# mainboard.net
KiCad netlist of a schematic drawn in EAGLE
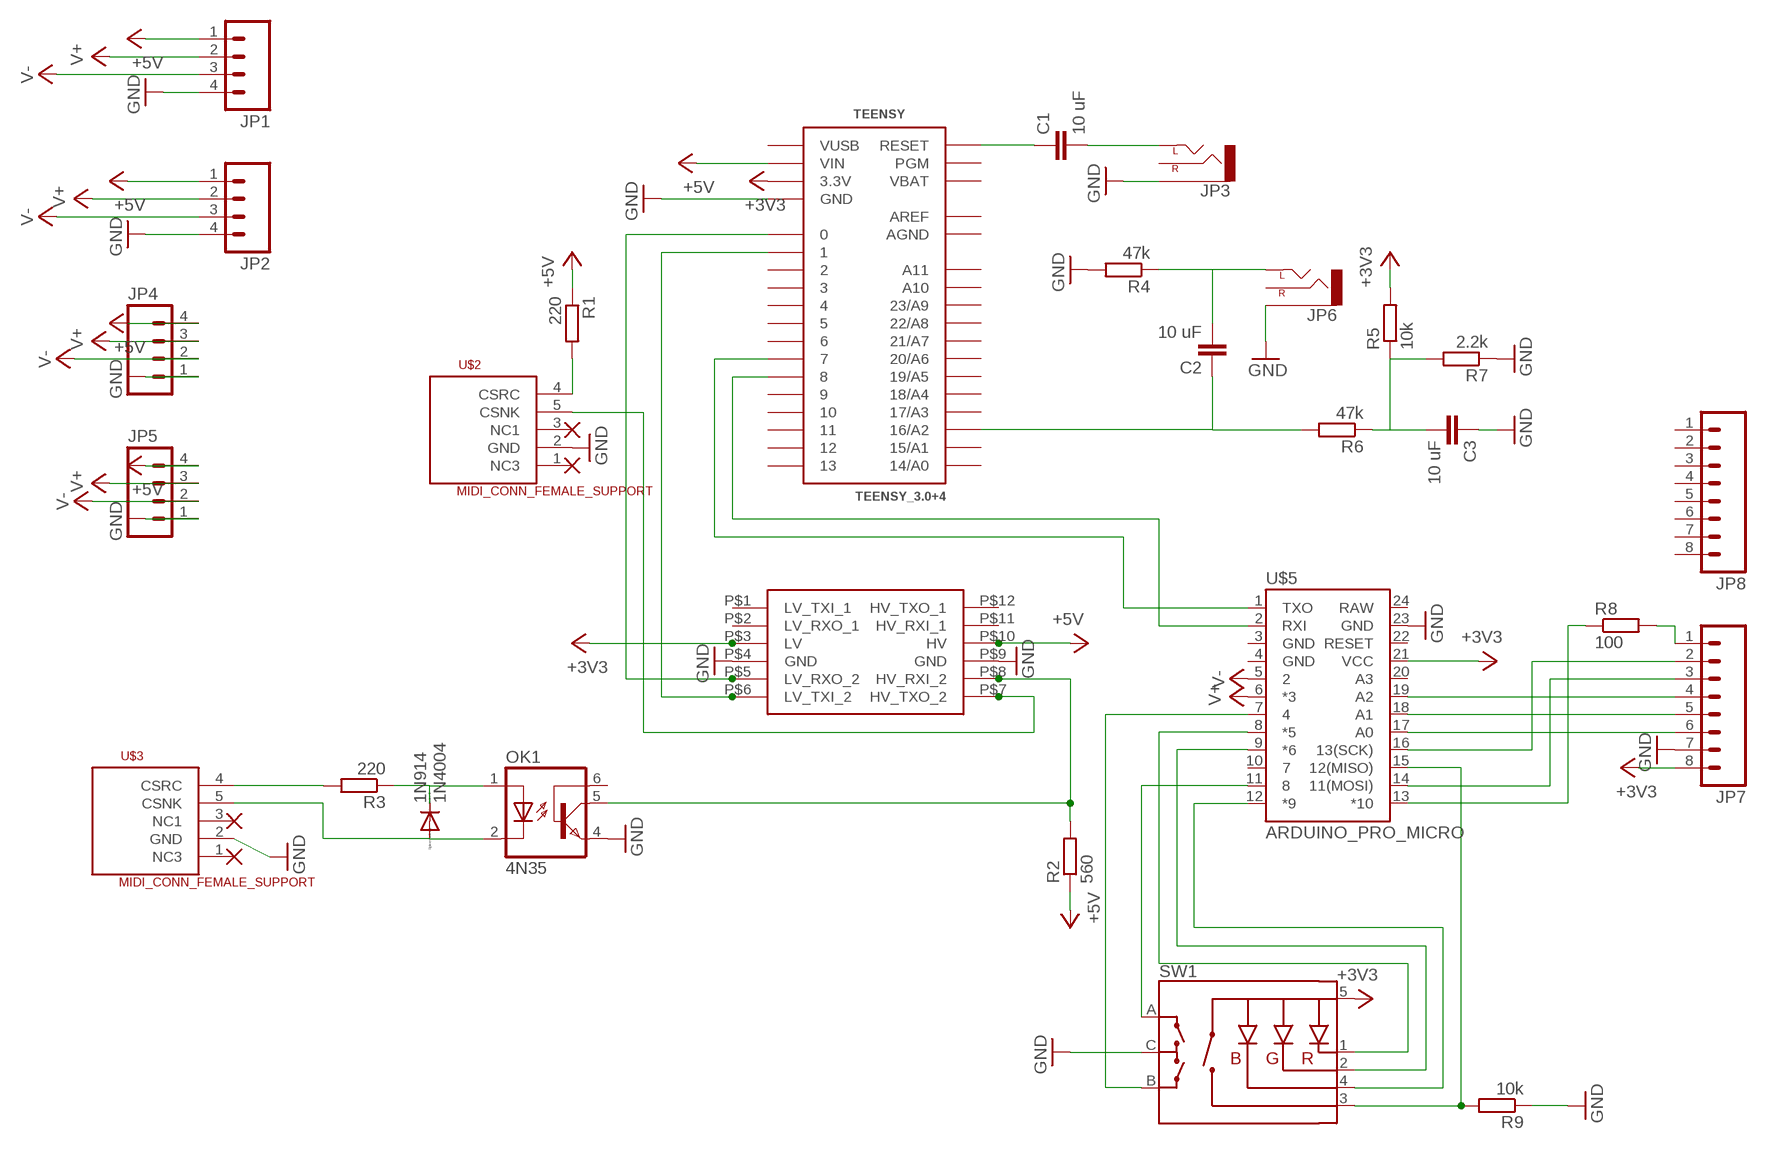
[diagram p0: schematic, sheet 1]

(export (version "E")
  (design (tool "Eeschema 10.0.6"))
  (components
    (comp (ref "1N914")
      (value "1N4004")
      (footprint "eagle-import:DO41-10")
      (libsource (lib "eagle-import") (part "1N4004"))
    )
    (comp (ref "C1")
      (value "10 uF")
      (footprint "eagle-import:CAP-PTH-SMALL")
      (libsource (lib "eagle-import") (part "CAPPTH"))
    )
    (comp (ref "C2")
      (value "10 uF")
      (footprint "eagle-import:CAP-PTH-SMALL")
      (libsource (lib "eagle-import") (part "CAPPTH"))
    )
    (comp (ref "C3")
      (value "10 uF")
      (footprint "eagle-import:CAP-PTH-SMALL")
      (libsource (lib "eagle-import") (part "CAPPTH"))
    )
    (comp (ref "JP1")
      (value "M04PTH")
      (footprint "eagle-import:1X04")
      (libsource (lib "eagle-import") (part "M04PTH"))
    )
    (comp (ref "JP2")
      (value "M04PTH")
      (footprint "eagle-import:1X04")
      (libsource (lib "eagle-import") (part "M04PTH"))
    )
    (comp (ref "JP3")
      (value "AUDIO-JACKPTH")
      (footprint "eagle-import:AUDIO-JACK")
      (libsource (lib "eagle-import") (part "AUDIO-JACKPTH"))
    )
    (comp (ref "JP4")
      (value "M04PTH")
      (footprint "eagle-import:1X04")
      (libsource (lib "eagle-import") (part "M04PTH"))
    )
    (comp (ref "JP5")
      (value "M04PTH")
      (footprint "eagle-import:1X04")
      (libsource (lib "eagle-import") (part "M04PTH"))
    )
    (comp (ref "JP6")
      (value "AUDIO-JACKPTH")
      (footprint "eagle-import:AUDIO-JACK")
      (libsource (lib "eagle-import") (part "AUDIO-JACKPTH"))
    )
    (comp (ref "JP7")
      (value "M08")
      (footprint "eagle-import:1X08_ROUND")
      (libsource (lib "eagle-import") (part "M08"))
    )
    (comp (ref "JP8")
      (value "M08")
      (footprint "eagle-import:1X08_ROUND")
      (libsource (lib "eagle-import") (part "M08"))
    )
    (comp (ref "OK1")
      (value "4N35")
      (footprint "eagle-import:DIL06")
      (fields (field (name "MF") "FAIRCHILD SEMICONDUCTOR"))
      (libsource (lib "eagle-import") (part "4N35"))
    )
    (comp (ref "R1")
      (value "220")
      (footprint "eagle-import:0204_5")
      (libsource (lib "eagle-import") (part "R-EU_0204/5"))
    )
    (comp (ref "R2")
      (value "560")
      (footprint "eagle-import:0204_5")
      (libsource (lib "eagle-import") (part "R-EU_0204/5"))
    )
    (comp (ref "R3")
      (value "220")
      (footprint "eagle-import:0204_5")
      (libsource (lib "eagle-import") (part "R-EU_0204/5"))
    )
    (comp (ref "R4")
      (value "47k")
      (footprint "eagle-import:0204_5")
      (libsource (lib "eagle-import") (part "R-EU_0204/5"))
    )
    (comp (ref "R5")
      (value "10k")
      (footprint "eagle-import:0204_5")
      (libsource (lib "eagle-import") (part "R-EU_0204/5"))
    )
    (comp (ref "R6")
      (value "47k")
      (footprint "eagle-import:0204_5")
      (libsource (lib "eagle-import") (part "R-EU_0204/5"))
    )
    (comp (ref "R7")
      (value "2.2k")
      (footprint "eagle-import:0204_5")
      (libsource (lib "eagle-import") (part "R-EU_0204/5"))
    )
    (comp (ref "R8")
      (value "100")
      (footprint "eagle-import:0204_5")
      (libsource (lib "eagle-import") (part "R-EU_0204/5"))
    )
    (comp (ref "R9")
      (value "10k")
      (footprint "eagle-import:0204_5")
      (libsource (lib "eagle-import") (part "R-EU_0204/5"))
    )
    (comp (ref "SW1")
      (value "ENCODER_RGB_CA")
      (footprint "eagle-import:ENCODER_LED_3")
      (libsource (lib "eagle-import") (part "ENCODER_RGB_CA"))
    )
    (comp (ref "TEENSY")
      (value "TEENSY_3.0+4")
      (footprint "eagle-import:TEENSY_3.0+4")
      (libsource (lib "eagle-import") (part "TEENSY_3.0+4"))
    )
    (comp (ref "U$2")
      (value "MIDI_CONN_FEMALE_SUPPORT")
      (footprint "eagle-import:DIN_5_FEMALE_SUPPORT")
      (libsource (lib "eagle-import") (part "MIDI_CONN_FEMALE_SUPPORT"))
    )
    (comp (ref "U$3")
      (value "MIDI_CONN_FEMALE_SUPPORT")
      (footprint "eagle-import:DIN_5_FEMALE_SUPPORT")
      (libsource (lib "eagle-import") (part "MIDI_CONN_FEMALE_SUPPORT"))
    )
    (comp (ref "U$4")
      (value "LOGIC_LEVEL_CONVERTER")
      (footprint "eagle-import:LOGIC_LEVEL_CONVERTER")
      (libsource (lib "eagle-import") (part "LOGIC_LEVEL_CONVERTER"))
    )
    (comp (ref "U$5")
      (value "ARDUINO_PRO_MICRO")
      (footprint "eagle-import:ARDUINO_PRO_MICRO")
      (libsource (lib "eagle-import") (part "ARDUINO_PRO_MICRO"))
    )
  )
  (nets
    (net (code "1") (name "+3V3") (class "Default")
      (node (ref "JP7") (pin "8") (pinfunction "8_8") (pintype "passive"))
      (node (ref "R5") (pin "2") (pinfunction "2_2") (pintype "passive"))
      (node (ref "SW1") (pin "5") (pinfunction "+_5") (pintype "passive"))
      (node (ref "TEENSY") (pin "3.3V") (pinfunction "3.3V_3.3V") (pintype "power_in"))
      (node (ref "TEENSY") (pin "3.3V1") (pinfunction "3.3V_3.3V1") (pintype "power_in"))
      (node (ref "U$4") (pin "P$3") (pinfunction "LV_P$3") (pintype "bidirectional"))
      (node (ref "U$5") (pin "21") (pinfunction "VCC_21") (pintype "bidirectional"))
    )
    (net (code "2") (name "+5V") (class "Default")
      (node (ref "JP1") (pin "1") (pinfunction "1_1") (pintype "passive"))
      (node (ref "JP2") (pin "1") (pinfunction "1_1") (pintype "passive"))
      (node (ref "JP4") (pin "4") (pinfunction "4_4") (pintype "passive"))
      (node (ref "JP5") (pin "4") (pinfunction "4_4") (pintype "passive"))
      (node (ref "R1") (pin "1") (pinfunction "1_1") (pintype "passive"))
      (node (ref "R2") (pin "1") (pinfunction "1_1") (pintype "passive"))
      (node (ref "TEENSY") (pin "VIN") (pinfunction "VIN_VIN") (pintype "power_in"))
      (node (ref "U$4") (pin "P$10") (pinfunction "HV_P$10") (pintype "bidirectional"))
    )
    (net (code "3") (name "/AGND") (class "Default")
      (node (ref "TEENSY") (pin "AGND") (pinfunction "AGND_AGND") (pintype "power_in"))
    )
    (net (code "4") (name "/AREF") (class "Default")
      (node (ref "TEENSY") (pin "AREF") (pinfunction "AREF_AREF") (pintype "power_in"))
    )
    (net (code "5") (name "/VBAT") (class "Default")
      (node (ref "TEENSY") (pin "VBAT") (pinfunction "VBAT_VBAT") (pintype "power_in"))
    )
    (net (code "6") (name "/VUSB") (class "Default")
      (node (ref "TEENSY") (pin "VUSB") (pinfunction "VUSB_VUSB") (pintype "power_in"))
    )
    (net (code "7") (name "GND") (class "Default")
      (node (ref "C3") (pin "1") (pinfunction "1_1") (pintype "passive"))
      (node (ref "JP1") (pin "4") (pinfunction "4_4") (pintype "passive"))
      (node (ref "JP2") (pin "4") (pinfunction "4_4") (pintype "passive"))
      (node (ref "JP3") (pin "SLEEVE") (pinfunction "SLEEVE_SLEEVE") (pintype "bidirectional"))
      (node (ref "JP4") (pin "1") (pinfunction "1_1") (pintype "passive"))
      (node (ref "JP5") (pin "1") (pinfunction "1_1") (pintype "passive"))
      (node (ref "JP6") (pin "SLEEVE") (pinfunction "SLEEVE_SLEEVE") (pintype "bidirectional"))
      (node (ref "JP7") (pin "7") (pinfunction "7_7") (pintype "passive"))
      (node (ref "OK1") (pin "4") (pinfunction "EMI_4") (pintype "passive"))
      (node (ref "R4") (pin "2") (pinfunction "2_2") (pintype "passive"))
      (node (ref "R7") (pin "1") (pinfunction "1_1") (pintype "passive"))
      (node (ref "R9") (pin "1") (pinfunction "1_1") (pintype "passive"))
      (node (ref "SW1") (pin "C") (pinfunction "C_C") (pintype "bidirectional"))
      (node (ref "TEENSY") (pin "GND") (pinfunction "GND_GND") (pintype "power_in"))
      (node (ref "TEENSY") (pin "GND1") (pinfunction "GND_GND1") (pintype "power_in"))
      (node (ref "U$2") (pin "2") (pinfunction "GND_2") (pintype "bidirectional"))
      (node (ref "U$3") (pin "2") (pinfunction "GND_2") (pintype "bidirectional"))
      (node (ref "U$4") (pin "P$4") (pinfunction "GND_P$4") (pintype "bidirectional"))
      (node (ref "U$4") (pin "P$9") (pinfunction "GND_P$9") (pintype "bidirectional"))
      (node (ref "U$5") (pin "23") (pinfunction "GND_23") (pintype "bidirectional"))
    )
    (net (code "8") (name "Net-(C1-Pad1)") (class "Default")
      (node (ref "C1") (pin "1") (pinfunction "1_1") (pintype "passive"))
      (node (ref "TEENSY") (pin "RESET") (pinfunction "RESET_RESET") (pintype "bidirectional"))
    )
    (net (code "9") (name "Net-(C2-Pad1)") (class "Default")
      (node (ref "C2") (pin "1") (pinfunction "1_1") (pintype "passive"))
      (node (ref "R6") (pin "2") (pinfunction "2_2") (pintype "passive"))
      (node (ref "TEENSY") (pin "16/A2") (pinfunction "16/A2_16/A2") (pintype "bidirectional"))
    )
    (net (code "10") (name "Net-(C3-Pad2)") (class "Default")
      (node (ref "C3") (pin "2") (pinfunction "2_2") (pintype "passive"))
      (node (ref "R5") (pin "1") (pinfunction "1_1") (pintype "passive"))
      (node (ref "R6") (pin "1") (pinfunction "1_1") (pintype "passive"))
      (node (ref "R7") (pin "2") (pinfunction "2_2") (pintype "passive"))
    )
    (net (code "11") (name "Net-(JP3-LEFT)") (class "Default")
      (node (ref "C1") (pin "2") (pinfunction "2_2") (pintype "passive"))
      (node (ref "JP3") (pin "TIP") (pinfunction "LEFT_TIP") (pintype "bidirectional"))
    )
    (net (code "12") (name "Net-(JP6-LEFT)") (class "Default")
      (node (ref "C2") (pin "2") (pinfunction "2_2") (pintype "passive"))
      (node (ref "JP6") (pin "TIP") (pinfunction "LEFT_TIP") (pintype "bidirectional"))
      (node (ref "R4") (pin "1") (pinfunction "1_1") (pintype "passive"))
    )
    (net (code "13") (name "Net-(JP7-Pad1)") (class "Default")
      (node (ref "JP7") (pin "1") (pinfunction "1_1") (pintype "passive"))
      (node (ref "R8") (pin "2") (pinfunction "2_2") (pintype "passive"))
    )
    (net (code "14") (name "Net-(OK1-A)") (class "Default")
      (node (ref "1N914") (pin "C") (pinfunction "C_C") (pintype "passive"))
      (node (ref "OK1") (pin "1") (pinfunction "A_1") (pintype "passive"))
      (node (ref "R3") (pin "1") (pinfunction "1_1") (pintype "passive"))
    )
    (net (code "15") (name "Net-(OK1-C)") (class "Default")
      (node (ref "1N914") (pin "A") (pinfunction "A_A") (pintype "passive"))
      (node (ref "OK1") (pin "2") (pinfunction "C_2") (pintype "passive"))
      (node (ref "U$3") (pin "5") (pinfunction "CSNK_5") (pintype "bidirectional"))
    )
    (net (code "16") (name "Net-(OK1-COL)") (class "Default")
      (node (ref "OK1") (pin "5") (pinfunction "COL_5") (pintype "passive"))
      (node (ref "R2") (pin "2") (pinfunction "2_2") (pintype "passive"))
      (node (ref "U$4") (pin "P$8") (pinfunction "HV_RXI_2_P$8") (pintype "bidirectional"))
    )
    (net (code "17") (name "Net-(SW1--B)") (class "Default")
      (node (ref "SW1") (pin "4") (pinfunction "-B_4") (pintype "passive"))
      (node (ref "U$5") (pin "12") (pinfunction "*9_12") (pintype "bidirectional"))
    )
    (net (code "18") (name "Net-(SW1--G)") (class "Default")
      (node (ref "SW1") (pin "2") (pinfunction "-G_2") (pintype "passive"))
      (node (ref "U$5") (pin "9") (pinfunction "*6_9") (pintype "bidirectional"))
    )
    (net (code "19") (name "Net-(SW1--R)") (class "Default")
      (node (ref "SW1") (pin "1") (pinfunction "-R_1") (pintype "passive"))
      (node (ref "U$5") (pin "8") (pinfunction "*5_8") (pintype "bidirectional"))
    )
    (net (code "20") (name "Net-(SW1-SW)") (class "Default")
      (node (ref "R9") (pin "2") (pinfunction "2_2") (pintype "passive"))
      (node (ref "SW1") (pin "3") (pinfunction "SW_3") (pintype "passive"))
      (node (ref "U$5") (pin "15") (pinfunction "12(MISO)_15") (pintype "bidirectional"))
    )
    (net (code "21") (name "Net-(U$2-CSNK)") (class "Default")
      (node (ref "U$2") (pin "5") (pinfunction "CSNK_5") (pintype "bidirectional"))
      (node (ref "U$4") (pin "P$7") (pinfunction "HV_TXO_2_P$7") (pintype "bidirectional"))
    )
    (net (code "22") (name "Net-(U$2-CSRC)") (class "Default")
      (node (ref "R1") (pin "2") (pinfunction "2_2") (pintype "passive"))
      (node (ref "U$2") (pin "4") (pinfunction "CSRC_4") (pintype "bidirectional"))
    )
    (net (code "23") (name "Net-(U$3-CSRC)") (class "Default")
      (node (ref "R3") (pin "2") (pinfunction "2_2") (pintype "passive"))
      (node (ref "U$3") (pin "4") (pinfunction "CSRC_4") (pintype "bidirectional"))
    )
    (net (code "24") (name "Net-(U$4-LV_RXO_2)") (class "Default")
      (node (ref "TEENSY") (pin "0") (pinfunction "0_0") (pintype "bidirectional"))
      (node (ref "U$4") (pin "P$5") (pinfunction "LV_RXO_2_P$5") (pintype "bidirectional"))
    )
    (net (code "25") (name "Net-(U$4-LV_TXI_2)") (class "Default")
      (node (ref "TEENSY") (pin "1") (pinfunction "1_1") (pintype "bidirectional"))
      (node (ref "U$4") (pin "P$6") (pinfunction "LV_TXI_2_P$6") (pintype "bidirectional"))
    )
    (net (code "26") (name "Net-(U$5-*10)") (class "Default")
      (node (ref "R8") (pin "1") (pinfunction "1_1") (pintype "passive"))
      (node (ref "U$5") (pin "13") (pinfunction "*10_13") (pintype "bidirectional"))
    )
    (net (code "27") (name "Net-(U$5-4)") (class "Default")
      (node (ref "SW1") (pin "B") (pinfunction "B_B") (pintype "bidirectional"))
      (node (ref "U$5") (pin "7") (pinfunction "4_7") (pintype "bidirectional"))
    )
    (net (code "28") (name "Net-(U$5-8)") (class "Default")
      (node (ref "SW1") (pin "A") (pinfunction "A_A") (pintype "bidirectional"))
      (node (ref "U$5") (pin "11") (pinfunction "8_11") (pintype "bidirectional"))
    )
    (net (code "29") (name "Net-(U$5-11(MOSI))") (class "Default")
      (node (ref "JP7") (pin "3") (pinfunction "3_3") (pintype "passive"))
      (node (ref "U$5") (pin "14") (pinfunction "11(MOSI)_14") (pintype "bidirectional"))
    )
    (net (code "30") (name "Net-(U$5-13(SCK))") (class "Default")
      (node (ref "JP7") (pin "2") (pinfunction "2_2") (pintype "passive"))
      (node (ref "U$5") (pin "16") (pinfunction "13(SCK)_16") (pintype "bidirectional"))
    )
    (net (code "31") (name "Net-(U$5-A0)") (class "Default")
      (node (ref "JP7") (pin "6") (pinfunction "6_6") (pintype "passive"))
      (node (ref "U$5") (pin "17") (pinfunction "A0_17") (pintype "bidirectional"))
    )
    (net (code "32") (name "Net-(U$5-A1)") (class "Default")
      (node (ref "JP7") (pin "5") (pinfunction "5_5") (pintype "passive"))
      (node (ref "U$5") (pin "18") (pinfunction "A1_18") (pintype "bidirectional"))
    )
    (net (code "33") (name "Net-(U$5-A2)") (class "Default")
      (node (ref "JP7") (pin "4") (pinfunction "4_4") (pintype "passive"))
      (node (ref "U$5") (pin "19") (pinfunction "A2_19") (pintype "bidirectional"))
    )
    (net (code "34") (name "Net-(U$5-RXI)") (class "Default")
      (node (ref "TEENSY") (pin "8") (pinfunction "8_8") (pintype "bidirectional"))
      (node (ref "U$5") (pin "2") (pinfunction "RXI_2") (pintype "bidirectional"))
    )
    (net (code "35") (name "Net-(U$5-TXO)") (class "Default")
      (node (ref "TEENSY") (pin "7") (pinfunction "7_7") (pintype "bidirectional"))
      (node (ref "U$5") (pin "1") (pinfunction "TXO_1") (pintype "bidirectional"))
    )
    (net (code "36") (name "V+") (class "Default")
      (node (ref "JP1") (pin "2") (pinfunction "2_2") (pintype "passive"))
      (node (ref "JP2") (pin "2") (pinfunction "2_2") (pintype "passive"))
      (node (ref "JP4") (pin "3") (pinfunction "3_3") (pintype "passive"))
      (node (ref "JP5") (pin "3") (pinfunction "3_3") (pintype "passive"))
      (node (ref "U$5") (pin "6") (pinfunction "*3_6") (pintype "bidirectional"))
    )
    (net (code "37") (name "V-") (class "Default")
      (node (ref "JP1") (pin "3") (pinfunction "3_3") (pintype "passive"))
      (node (ref "JP2") (pin "3") (pinfunction "3_3") (pintype "passive"))
      (node (ref "JP4") (pin "2") (pinfunction "2_2") (pintype "passive"))
      (node (ref "JP5") (pin "2") (pinfunction "2_2") (pintype "passive"))
      (node (ref "U$5") (pin "5") (pinfunction "2_5") (pintype "bidirectional"))
    )
    (net (code "38") (name "unconnected-(JP3-RIGHT-PadRING)") (class "Default")
      (node (ref "JP3") (pin "RING") (pinfunction "RIGHT_RING") (pintype "bidirectional"))
    )
    (net (code "39") (name "unconnected-(JP6-RIGHT-PadRING)") (class "Default")
      (node (ref "JP6") (pin "RING") (pinfunction "RIGHT_RING") (pintype "bidirectional"))
    )
    (net (code "40") (name "unconnected-(JP8-Pad1)") (class "Default")
      (node (ref "JP8") (pin "1") (pinfunction "1_1") (pintype "passive"))
    )
    (net (code "41") (name "unconnected-(JP8-Pad2)") (class "Default")
      (node (ref "JP8") (pin "2") (pinfunction "2_2") (pintype "passive"))
    )
    (net (code "42") (name "unconnected-(JP8-Pad3)") (class "Default")
      (node (ref "JP8") (pin "3") (pinfunction "3_3") (pintype "passive"))
    )
    (net (code "43") (name "unconnected-(JP8-Pad4)") (class "Default")
      (node (ref "JP8") (pin "4") (pinfunction "4_4") (pintype "passive"))
    )
    (net (code "44") (name "unconnected-(JP8-Pad5)") (class "Default")
      (node (ref "JP8") (pin "5") (pinfunction "5_5") (pintype "passive"))
    )
    (net (code "45") (name "unconnected-(JP8-Pad6)") (class "Default")
      (node (ref "JP8") (pin "6") (pinfunction "6_6") (pintype "passive"))
    )
    (net (code "46") (name "unconnected-(JP8-Pad7)") (class "Default")
      (node (ref "JP8") (pin "7") (pinfunction "7_7") (pintype "passive"))
    )
    (net (code "47") (name "unconnected-(JP8-Pad8)") (class "Default")
      (node (ref "JP8") (pin "8") (pinfunction "8_8") (pintype "passive"))
    )
    (net (code "48") (name "unconnected-(OK1-BAS-Pad6)") (class "Default")
      (node (ref "OK1") (pin "6") (pinfunction "BAS_6") (pintype "passive"))
    )
    (net (code "49") (name "unconnected-(TEENSY-Pad2)") (class "Default")
      (node (ref "TEENSY") (pin "2") (pinfunction "2_2") (pintype "bidirectional"))
    )
    (net (code "50") (name "unconnected-(TEENSY-Pad3)") (class "Default")
      (node (ref "TEENSY") (pin "3") (pinfunction "3_3") (pintype "bidirectional"))
    )
    (net (code "51") (name "unconnected-(TEENSY-Pad4)") (class "Default")
      (node (ref "TEENSY") (pin "4") (pinfunction "4_4") (pintype "bidirectional"))
    )
    (net (code "52") (name "unconnected-(TEENSY-Pad5)") (class "Default")
      (node (ref "TEENSY") (pin "5") (pinfunction "5_5") (pintype "bidirectional"))
    )
    (net (code "53") (name "unconnected-(TEENSY-Pad6)") (class "Default")
      (node (ref "TEENSY") (pin "6") (pinfunction "6_6") (pintype "bidirectional"))
    )
    (net (code "54") (name "unconnected-(TEENSY-Pad9)") (class "Default")
      (node (ref "TEENSY") (pin "9") (pinfunction "9_9") (pintype "bidirectional"))
    )
    (net (code "55") (name "unconnected-(TEENSY-Pad10)") (class "Default")
      (node (ref "TEENSY") (pin "10") (pinfunction "10_10") (pintype "bidirectional"))
    )
    (net (code "56") (name "unconnected-(TEENSY-Pad11)") (class "Default")
      (node (ref "TEENSY") (pin "11") (pinfunction "11_11") (pintype "bidirectional"))
    )
    (net (code "57") (name "unconnected-(TEENSY-Pad12)") (class "Default")
      (node (ref "TEENSY") (pin "12") (pinfunction "12_12") (pintype "bidirectional"))
    )
    (net (code "58") (name "unconnected-(TEENSY-Pad13)") (class "Default")
      (node (ref "TEENSY") (pin "13") (pinfunction "13_13") (pintype "bidirectional"))
    )
    (net (code "59") (name "unconnected-(TEENSY-Pad14{slash}A0)") (class "Default")
      (node (ref "TEENSY") (pin "14/A0") (pinfunction "14/A0_14/A0") (pintype "bidirectional"))
    )
    (net (code "60") (name "unconnected-(TEENSY-Pad15{slash}A1)") (class "Default")
      (node (ref "TEENSY") (pin "15/A1") (pinfunction "15/A1_15/A1") (pintype "bidirectional"))
    )
    (net (code "61") (name "unconnected-(TEENSY-Pad17{slash}A3)") (class "Default")
      (node (ref "TEENSY") (pin "17/A3") (pinfunction "17/A3_17/A3") (pintype "bidirectional"))
    )
    (net (code "62") (name "unconnected-(TEENSY-Pad18{slash}A4)") (class "Default")
      (node (ref "TEENSY") (pin "18/A4") (pinfunction "18/A4_18/A4") (pintype "bidirectional"))
    )
    (net (code "63") (name "unconnected-(TEENSY-Pad19{slash}A5)") (class "Default")
      (node (ref "TEENSY") (pin "19/A5") (pinfunction "19/A5_19/A5") (pintype "bidirectional"))
    )
    (net (code "64") (name "unconnected-(TEENSY-Pad20{slash}A6)") (class "Default")
      (node (ref "TEENSY") (pin "20/A6") (pinfunction "20/A6_20/A6") (pintype "bidirectional"))
    )
    (net (code "65") (name "unconnected-(TEENSY-Pad21{slash}A7)") (class "Default")
      (node (ref "TEENSY") (pin "21/A7") (pinfunction "21/A7_21/A7") (pintype "bidirectional"))
    )
    (net (code "66") (name "unconnected-(TEENSY-Pad22{slash}A8)") (class "Default")
      (node (ref "TEENSY") (pin "22/A8") (pinfunction "22/A8_22/A8") (pintype "bidirectional"))
    )
    (net (code "67") (name "unconnected-(TEENSY-Pad23{slash}A9)") (class "Default")
      (node (ref "TEENSY") (pin "23/A9") (pinfunction "23/A9_23/A9") (pintype "bidirectional"))
    )
    (net (code "68") (name "unconnected-(TEENSY-PadA10)") (class "Default")
      (node (ref "TEENSY") (pin "A10") (pinfunction "A10_A10") (pintype "bidirectional"))
    )
    (net (code "69") (name "unconnected-(TEENSY-PadA11)") (class "Default")
      (node (ref "TEENSY") (pin "A11") (pinfunction "A11_A11") (pintype "bidirectional"))
    )
    (net (code "70") (name "unconnected-(TEENSY-PadPGM)") (class "Default")
      (node (ref "TEENSY") (pin "PGM") (pinfunction "PGM_PGM") (pintype "bidirectional"))
    )
    (net (code "71") (name "unconnected-(U$2-NC1-Pad3)") (class "Default")
      (node (ref "U$2") (pin "3") (pinfunction "NC1_3") (pintype "bidirectional"))
    )
    (net (code "72") (name "unconnected-(U$2-NC3-Pad1)") (class "Default")
      (node (ref "U$2") (pin "1") (pinfunction "NC3_1") (pintype "bidirectional"))
    )
    (net (code "73") (name "unconnected-(U$3-NC1-Pad3)") (class "Default")
      (node (ref "U$3") (pin "3") (pinfunction "NC1_3") (pintype "bidirectional"))
    )
    (net (code "74") (name "unconnected-(U$3-NC3-Pad1)") (class "Default")
      (node (ref "U$3") (pin "1") (pinfunction "NC3_1") (pintype "bidirectional"))
    )
    (net (code "75") (name "unconnected-(U$4-HV_RXI_1-PadP$11)") (class "Default")
      (node (ref "U$4") (pin "P$11") (pinfunction "HV_RXI_1_P$11") (pintype "bidirectional"))
    )
    (net (code "76") (name "unconnected-(U$4-HV_TXO_1-PadP$12)") (class "Default")
      (node (ref "U$4") (pin "P$12") (pinfunction "HV_TXO_1_P$12") (pintype "bidirectional"))
    )
    (net (code "77") (name "unconnected-(U$4-LV_RXO_1-PadP$2)") (class "Default")
      (node (ref "U$4") (pin "P$2") (pinfunction "LV_RXO_1_P$2") (pintype "bidirectional"))
    )
    (net (code "78") (name "unconnected-(U$4-LV_TXI_1-PadP$1)") (class "Default")
      (node (ref "U$4") (pin "P$1") (pinfunction "LV_TXI_1_P$1") (pintype "bidirectional"))
    )
    (net (code "79") (name "unconnected-(U$5-7-Pad10)") (class "Default")
      (node (ref "U$5") (pin "10") (pinfunction "7_10") (pintype "bidirectional"))
    )
    (net (code "80") (name "unconnected-(U$5-A3-Pad20)") (class "Default")
      (node (ref "U$5") (pin "20") (pinfunction "A3_20") (pintype "bidirectional"))
    )
    (net (code "81") (name "unconnected-(U$5-GND-Pad3)") (class "Default")
      (node (ref "U$5") (pin "3") (pinfunction "GND_3") (pintype "bidirectional"))
    )
    (net (code "82") (name "unconnected-(U$5-GND-Pad4)") (class "Default")
      (node (ref "U$5") (pin "4") (pinfunction "GND_4") (pintype "bidirectional"))
    )
    (net (code "83") (name "unconnected-(U$5-RAW-Pad24)") (class "Default")
      (node (ref "U$5") (pin "24") (pinfunction "RAW_24") (pintype "bidirectional"))
    )
    (net (code "84") (name "unconnected-(U$5-RESET-Pad22)") (class "Default")
      (node (ref "U$5") (pin "22") (pinfunction "RESET_22") (pintype "bidirectional"))
    )
  )
)
